# so08b.net
KiCad netlist of a schematic drawn in EAGLE
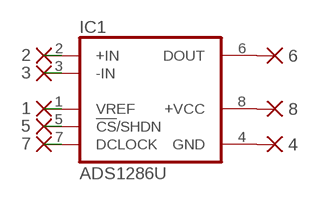
[diagram p0: schematic, sheet 1]

(export (version "E")
  (design (tool "Eeschema 10.0.6"))
  (components
    (comp (ref "1")
      (value "PAD-0360")
      (footprint "eagle-import:0360")
      (libsource (lib "eagle-import") (part "PAD-0360"))
    )
    (comp (ref "2")
      (value "PAD-0360")
      (footprint "eagle-import:0360")
      (libsource (lib "eagle-import") (part "PAD-0360"))
    )
    (comp (ref "3")
      (value "PAD-0360")
      (footprint "eagle-import:0360")
      (libsource (lib "eagle-import") (part "PAD-0360"))
    )
    (comp (ref "4")
      (value "PAD-0360")
      (footprint "eagle-import:0360")
      (libsource (lib "eagle-import") (part "PAD-0360"))
    )
    (comp (ref "5")
      (value "PAD-0360")
      (footprint "eagle-import:0360")
      (libsource (lib "eagle-import") (part "PAD-0360"))
    )
    (comp (ref "6")
      (value "PAD-0360")
      (footprint "eagle-import:0360")
      (libsource (lib "eagle-import") (part "PAD-0360"))
    )
    (comp (ref "7")
      (value "PAD-0360")
      (footprint "eagle-import:0360")
      (libsource (lib "eagle-import") (part "PAD-0360"))
    )
    (comp (ref "8")
      (value "PAD-0360")
      (footprint "eagle-import:0360")
      (libsource (lib "eagle-import") (part "PAD-0360"))
    )
    (comp (ref "IC1")
      (value "ADS1286U")
      (footprint "eagle-import:SO08")
      (fields (field (name "MF") "TEXAS INSTRUMENTS"))
      (libsource (lib "eagle-import") (part "ADS1286U"))
    )
  )
  (nets
    (net (code "1") (name "Net-(1-P)") (class "Default")
      (node (ref "1") (pin "P$1") (pinfunction "P_P$1") (pintype "passive"))
      (node (ref "IC1") (pin "1") (pinfunction "VREF_1") (pintype "input"))
    )
    (net (code "2") (name "Net-(2-P)") (class "Default")
      (node (ref "2") (pin "P$1") (pinfunction "P_P$1") (pintype "passive"))
      (node (ref "IC1") (pin "2") (pinfunction "+IN_2") (pintype "input"))
    )
    (net (code "3") (name "Net-(3-P)") (class "Default")
      (node (ref "3") (pin "P$1") (pinfunction "P_P$1") (pintype "passive"))
      (node (ref "IC1") (pin "3") (pinfunction "-IN_3") (pintype "input"))
    )
    (net (code "4") (name "Net-(4-P)") (class "Default")
      (node (ref "4") (pin "P$1") (pinfunction "P_P$1") (pintype "passive"))
      (node (ref "IC1") (pin "4") (pinfunction "GND_4") (pintype "power_in"))
    )
    (net (code "5") (name "Net-(5-P)") (class "Default")
      (node (ref "5") (pin "P$1") (pinfunction "P_P$1") (pintype "passive"))
      (node (ref "IC1") (pin "5") (pinfunction "~{CS}/SHDN_5") (pintype "input"))
    )
    (net (code "6") (name "Net-(6-P)") (class "Default")
      (node (ref "6") (pin "P$1") (pinfunction "P_P$1") (pintype "passive"))
      (node (ref "IC1") (pin "6") (pinfunction "DOUT_6") (pintype "output"))
    )
    (net (code "7") (name "Net-(7-P)") (class "Default")
      (node (ref "7") (pin "P$1") (pinfunction "P_P$1") (pintype "passive"))
      (node (ref "IC1") (pin "7") (pinfunction "DCLOCK_7") (pintype "input"))
    )
    (net (code "8") (name "Net-(8-P)") (class "Default")
      (node (ref "8") (pin "P$1") (pinfunction "P_P$1") (pintype "passive"))
      (node (ref "IC1") (pin "8") (pinfunction "+VCC_8") (pintype "power_in"))
    )
  )
)
